# H723ZG_Interface.net
KiCad netlist of a schematic drawn in Altium Designer
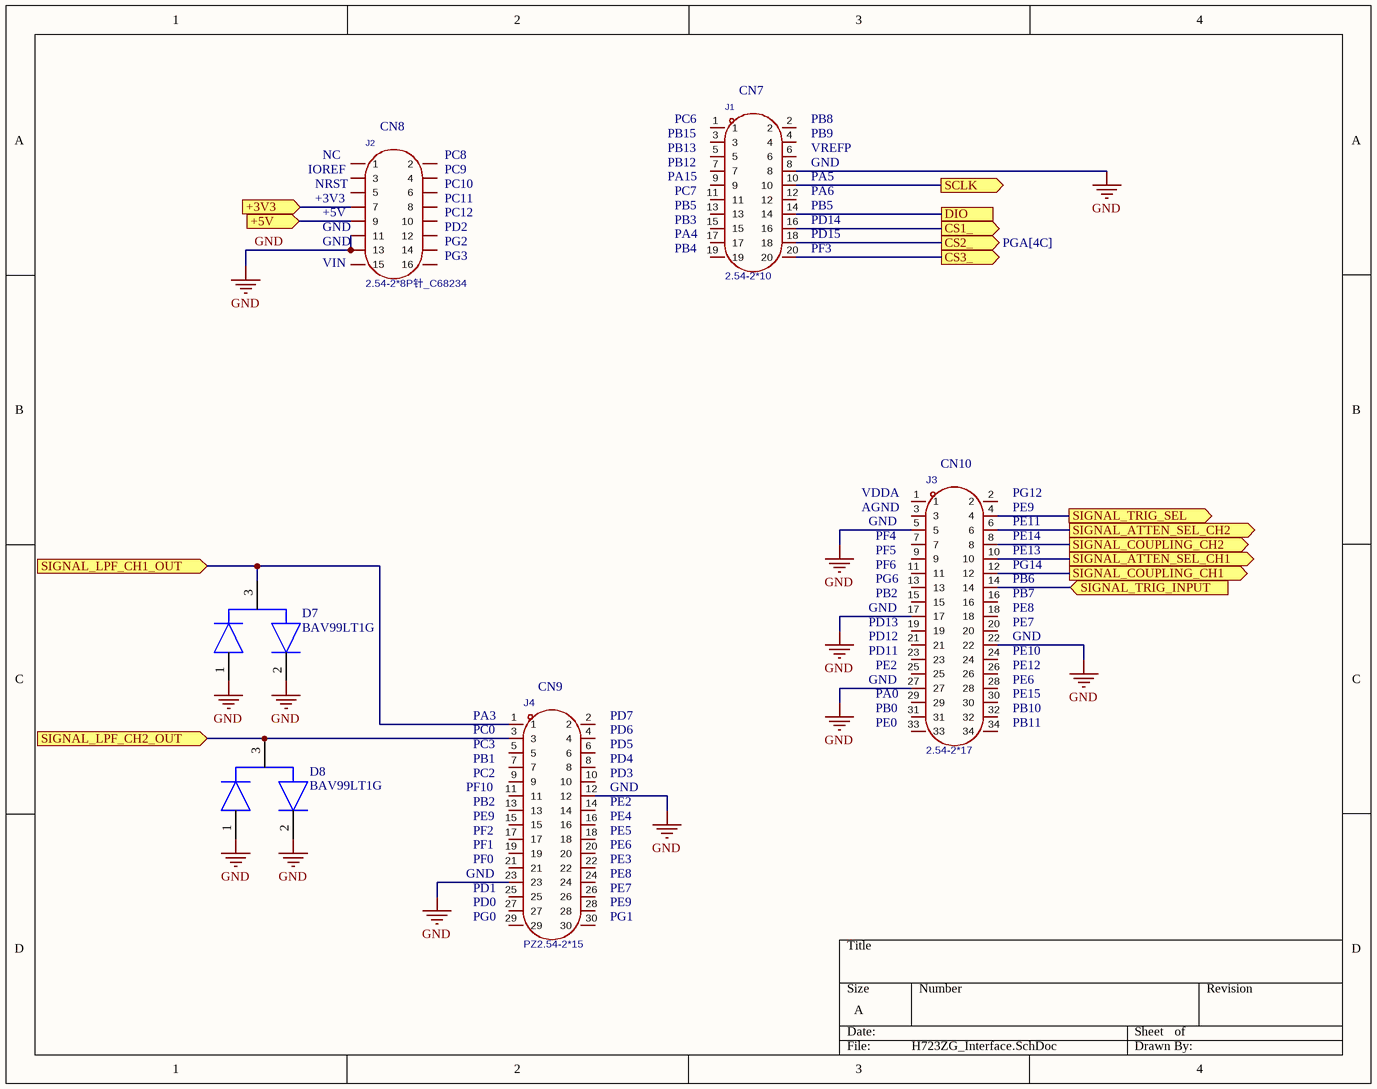
[diagram p0: H723ZG_Interface.SchDoc]

(export (version "E")
  (design (tool "Eeschema 10.0.6"))
  (components
    (comp (ref "D7")
      (value "BAV99LT1G")
      (footprint "FP-318-08-IPC_B")
      (description "DIODE ARRAY 100V 215MA SOT23-3")
      (libsource (lib "Altium Content Vault") (part "7b418a28e9680f52904df7990ac9ce6"))
    )
    (comp (ref "D8")
      (value "BAV99LT1G")
      (footprint "FP-318-08-IPC_B")
      (description "DIODE ARRAY 100V 215MA SOT23-3")
      (libsource (lib "Altium Content Vault") (part "7b418a28e9680f52904df7990ac9ce6"))
    )
    (comp (ref "J1")
      (value "2.54-2*10")
      (footprint "HDR-TH_20P-P2.54-V-M-R2-C10-S2.54")
      (fields (field (name "MANUFACTURER") "ZHOURI(洲日)"))
      (libsource (lib "zhiming xue") (part "2.54-2*10"))
    )
    (comp (ref "J2")
      (value "2.54-2*8P针_C68234")
      (footprint "HDR-TH_16P-P2.54-V-M-R2-C8-S2.54")
      (fields
        (field (name "MANUFACTURER") "BOOMELE(博穆精密)")
        (field (name "MANUFACTURER PART NUMBER") "2.54-2*8P针")
      )
      (libsource (lib "zhiming xue") (part "2.54-2*8P针_C68234"))
    )
    (comp (ref "J3")
      (value "2.54-2*17")
      (footprint "HDR-TH_34P-P2.54-V-M-R2-C17-S2.54-2")
      (description "2.54mm pitch, 2 rows, 2*17, 34 pins total")
      (libsource (lib "zhiming xue") (part "PZ2.54-2*17"))
    )
    (comp (ref "J4")
      (value "PZ2.54-2*15")
      (footprint "HDR-TH_30P-P2.54-V-M-R2-C15-S2.54-2")
      (fields (field (name "MANUFACTURER") "ZHOURI(洲日)"))
      (libsource (lib "zhiming xue") (part "PZ2.54-2*15"))
    )
  )
  (nets
    (net (code "1") (name "/+3V3") (class "Default")
      (node (ref "J2") (pin "7") (pinfunction "7_7") (pintype "passive"))
    )
    (net (code "2") (name "/+5V") (class "Default")
      (node (ref "J2") (pin "9") (pinfunction "9_9") (pintype "passive"))
    )
    (net (code "3") (name "/CS1_") (class "Default")
      (node (ref "J1") (pin "16") (pinfunction "16_16") (pintype "passive"))
    )
    (net (code "4") (name "/CS2_") (class "Default")
      (node (ref "J1") (pin "18") (pinfunction "18_18") (pintype "passive"))
    )
    (net (code "5") (name "/CS3_") (class "Default")
      (node (ref "J1") (pin "20") (pinfunction "20_20") (pintype "passive"))
    )
    (net (code "6") (name "/DIO") (class "Default")
      (node (ref "J1") (pin "14") (pinfunction "14_14") (pintype "passive"))
    )
    (net (code "7") (name "/SCLK") (class "Default")
      (node (ref "J1") (pin "10") (pinfunction "10_10") (pintype "passive"))
    )
    (net (code "8") (name "/SIGNAL_ATTEN_SEL_CH1") (class "Default")
      (node (ref "J3") (pin "10") (pinfunction "10_10") (pintype "passive"))
    )
    (net (code "9") (name "/SIGNAL_ATTEN_SEL_CH2") (class "Default")
      (node (ref "J3") (pin "6") (pinfunction "6_6") (pintype "passive"))
    )
    (net (code "10") (name "/SIGNAL_COUPLING_CH1") (class "Default")
      (node (ref "J3") (pin "12") (pinfunction "12_12") (pintype "passive"))
    )
    (net (code "11") (name "/SIGNAL_COUPLING_CH2") (class "Default")
      (node (ref "J3") (pin "8") (pinfunction "8_8") (pintype "passive"))
    )
    (net (code "12") (name "/SIGNAL_LPF_CH1_OUT") (class "Default")
      (node (ref "D7") (pin "3") (pinfunction "CATHODE/ANODE_3") (pintype "passive"))
      (node (ref "J4") (pin "1") (pinfunction "1_1") (pintype "passive"))
    )
    (net (code "13") (name "/SIGNAL_LPF_CH2_OUT") (class "Default")
      (node (ref "D8") (pin "3") (pinfunction "CATHODE/ANODE_3") (pintype "passive"))
      (node (ref "J4") (pin "3") (pinfunction "3_3") (pintype "passive"))
    )
    (net (code "14") (name "/SIGNAL_TRIG_INPUT") (class "Default")
      (node (ref "J3") (pin "14") (pinfunction "14_14") (pintype "passive"))
    )
    (net (code "15") (name "/SIGNAL_TRIG_SEL") (class "Default")
      (node (ref "J3") (pin "4") (pinfunction "4_4") (pintype "passive"))
    )
    (net (code "16") (name "GND") (class "Default")
      (node (ref "D7") (pin "1") (pinfunction "A_1") (pintype "passive"))
      (node (ref "D7") (pin "2") (pinfunction "C_2") (pintype "passive"))
      (node (ref "D8") (pin "1") (pinfunction "A_1") (pintype "passive"))
      (node (ref "D8") (pin "2") (pinfunction "C_2") (pintype "passive"))
      (node (ref "J1") (pin "8") (pinfunction "8_8") (pintype "passive"))
      (node (ref "J2") (pin "11") (pinfunction "11_11") (pintype "passive"))
      (node (ref "J2") (pin "13") (pinfunction "13_13") (pintype "passive"))
      (node (ref "J3") (pin "17") (pinfunction "17_17") (pintype "passive"))
      (node (ref "J3") (pin "22") (pinfunction "22_22") (pintype "passive"))
      (node (ref "J3") (pin "27") (pinfunction "27_27") (pintype "passive"))
      (node (ref "J3") (pin "5") (pinfunction "5_5") (pintype "passive"))
      (node (ref "J4") (pin "12") (pinfunction "12_12") (pintype "passive"))
      (node (ref "J4") (pin "23") (pinfunction "23_23") (pintype "passive"))
    )
    (net (code "17") (name "unconnected-(J1-Pad1)") (class "Default")
      (node (ref "J1") (pin "1") (pinfunction "1_1") (pintype "passive"))
    )
    (net (code "18") (name "unconnected-(J1-Pad2)") (class "Default")
      (node (ref "J1") (pin "2") (pinfunction "2_2") (pintype "passive"))
    )
    (net (code "19") (name "unconnected-(J1-Pad3)") (class "Default")
      (node (ref "J1") (pin "3") (pinfunction "3_3") (pintype "passive"))
    )
    (net (code "20") (name "unconnected-(J1-Pad4)") (class "Default")
      (node (ref "J1") (pin "4") (pinfunction "4_4") (pintype "passive"))
    )
    (net (code "21") (name "unconnected-(J1-Pad5)") (class "Default")
      (node (ref "J1") (pin "5") (pinfunction "5_5") (pintype "passive"))
    )
    (net (code "22") (name "unconnected-(J1-Pad6)") (class "Default")
      (node (ref "J1") (pin "6") (pinfunction "6_6") (pintype "passive"))
    )
    (net (code "23") (name "unconnected-(J1-Pad7)") (class "Default")
      (node (ref "J1") (pin "7") (pinfunction "7_7") (pintype "passive"))
    )
    (net (code "24") (name "unconnected-(J1-Pad9)") (class "Default")
      (node (ref "J1") (pin "9") (pinfunction "9_9") (pintype "passive"))
    )
    (net (code "25") (name "unconnected-(J1-Pad11)") (class "Default")
      (node (ref "J1") (pin "11") (pinfunction "11_11") (pintype "passive"))
    )
    (net (code "26") (name "unconnected-(J1-Pad12)") (class "Default")
      (node (ref "J1") (pin "12") (pinfunction "12_12") (pintype "passive"))
    )
    (net (code "27") (name "unconnected-(J1-Pad13)") (class "Default")
      (node (ref "J1") (pin "13") (pinfunction "13_13") (pintype "passive"))
    )
    (net (code "28") (name "unconnected-(J1-Pad15)") (class "Default")
      (node (ref "J1") (pin "15") (pinfunction "15_15") (pintype "passive"))
    )
    (net (code "29") (name "unconnected-(J1-Pad17)") (class "Default")
      (node (ref "J1") (pin "17") (pinfunction "17_17") (pintype "passive"))
    )
    (net (code "30") (name "unconnected-(J1-Pad19)") (class "Default")
      (node (ref "J1") (pin "19") (pinfunction "19_19") (pintype "passive"))
    )
    (net (code "31") (name "unconnected-(J2-Pad1)") (class "Default")
      (node (ref "J2") (pin "1") (pinfunction "1_1") (pintype "passive"))
    )
    (net (code "32") (name "unconnected-(J2-Pad2)") (class "Default")
      (node (ref "J2") (pin "2") (pinfunction "2_2") (pintype "passive"))
    )
    (net (code "33") (name "unconnected-(J2-Pad3)") (class "Default")
      (node (ref "J2") (pin "3") (pinfunction "3_3") (pintype "passive"))
    )
    (net (code "34") (name "unconnected-(J2-Pad4)") (class "Default")
      (node (ref "J2") (pin "4") (pinfunction "4_4") (pintype "passive"))
    )
    (net (code "35") (name "unconnected-(J2-Pad5)") (class "Default")
      (node (ref "J2") (pin "5") (pinfunction "5_5") (pintype "passive"))
    )
    (net (code "36") (name "unconnected-(J2-Pad6)") (class "Default")
      (node (ref "J2") (pin "6") (pinfunction "6_6") (pintype "passive"))
    )
    (net (code "37") (name "unconnected-(J2-Pad8)") (class "Default")
      (node (ref "J2") (pin "8") (pinfunction "8_8") (pintype "passive"))
    )
    (net (code "38") (name "unconnected-(J2-Pad10)") (class "Default")
      (node (ref "J2") (pin "10") (pinfunction "10_10") (pintype "passive"))
    )
    (net (code "39") (name "unconnected-(J2-Pad12)") (class "Default")
      (node (ref "J2") (pin "12") (pinfunction "12_12") (pintype "passive"))
    )
    (net (code "40") (name "unconnected-(J2-Pad14)") (class "Default")
      (node (ref "J2") (pin "14") (pinfunction "14_14") (pintype "passive"))
    )
    (net (code "41") (name "unconnected-(J2-Pad15)") (class "Default")
      (node (ref "J2") (pin "15") (pinfunction "15_15") (pintype "passive"))
    )
    (net (code "42") (name "unconnected-(J2-Pad16)") (class "Default")
      (node (ref "J2") (pin "16") (pinfunction "16_16") (pintype "passive"))
    )
    (net (code "43") (name "unconnected-(J3-Pad1)") (class "Default")
      (node (ref "J3") (pin "1") (pinfunction "1_1") (pintype "passive"))
    )
    (net (code "44") (name "unconnected-(J3-Pad2)") (class "Default")
      (node (ref "J3") (pin "2") (pinfunction "2_2") (pintype "passive"))
    )
    (net (code "45") (name "unconnected-(J3-Pad3)") (class "Default")
      (node (ref "J3") (pin "3") (pinfunction "3_3") (pintype "passive"))
    )
    (net (code "46") (name "unconnected-(J3-Pad7)") (class "Default")
      (node (ref "J3") (pin "7") (pinfunction "7_7") (pintype "passive"))
    )
    (net (code "47") (name "unconnected-(J3-Pad9)") (class "Default")
      (node (ref "J3") (pin "9") (pinfunction "9_9") (pintype "passive"))
    )
    (net (code "48") (name "unconnected-(J3-Pad11)") (class "Default")
      (node (ref "J3") (pin "11") (pinfunction "11_11") (pintype "passive"))
    )
    (net (code "49") (name "unconnected-(J3-Pad13)") (class "Default")
      (node (ref "J3") (pin "13") (pinfunction "13_13") (pintype "passive"))
    )
    (net (code "50") (name "unconnected-(J3-Pad15)") (class "Default")
      (node (ref "J3") (pin "15") (pinfunction "15_15") (pintype "passive"))
    )
    (net (code "51") (name "unconnected-(J3-Pad16)") (class "Default")
      (node (ref "J3") (pin "16") (pinfunction "16_16") (pintype "passive"))
    )
    (net (code "52") (name "unconnected-(J3-Pad18)") (class "Default")
      (node (ref "J3") (pin "18") (pinfunction "18_18") (pintype "passive"))
    )
    (net (code "53") (name "unconnected-(J3-Pad19)") (class "Default")
      (node (ref "J3") (pin "19") (pinfunction "19_19") (pintype "passive"))
    )
    (net (code "54") (name "unconnected-(J3-Pad20)") (class "Default")
      (node (ref "J3") (pin "20") (pinfunction "20_20") (pintype "passive"))
    )
    (net (code "55") (name "unconnected-(J3-Pad21)") (class "Default")
      (node (ref "J3") (pin "21") (pinfunction "21_21") (pintype "passive"))
    )
    (net (code "56") (name "unconnected-(J3-Pad23)") (class "Default")
      (node (ref "J3") (pin "23") (pinfunction "23_23") (pintype "passive"))
    )
    (net (code "57") (name "unconnected-(J3-Pad24)") (class "Default")
      (node (ref "J3") (pin "24") (pinfunction "24_24") (pintype "passive"))
    )
    (net (code "58") (name "unconnected-(J3-Pad25)") (class "Default")
      (node (ref "J3") (pin "25") (pinfunction "25_25") (pintype "passive"))
    )
    (net (code "59") (name "unconnected-(J3-Pad26)") (class "Default")
      (node (ref "J3") (pin "26") (pinfunction "26_26") (pintype "passive"))
    )
    (net (code "60") (name "unconnected-(J3-Pad28)") (class "Default")
      (node (ref "J3") (pin "28") (pinfunction "28_28") (pintype "passive"))
    )
    (net (code "61") (name "unconnected-(J3-Pad29)") (class "Default")
      (node (ref "J3") (pin "29") (pinfunction "29_29") (pintype "passive"))
    )
    (net (code "62") (name "unconnected-(J3-Pad30)") (class "Default")
      (node (ref "J3") (pin "30") (pinfunction "30_30") (pintype "passive"))
    )
    (net (code "63") (name "unconnected-(J3-Pad31)") (class "Default")
      (node (ref "J3") (pin "31") (pinfunction "31_31") (pintype "passive"))
    )
    (net (code "64") (name "unconnected-(J3-Pad32)") (class "Default")
      (node (ref "J3") (pin "32") (pinfunction "32_32") (pintype "passive"))
    )
    (net (code "65") (name "unconnected-(J3-Pad33)") (class "Default")
      (node (ref "J3") (pin "33") (pinfunction "33_33") (pintype "passive"))
    )
    (net (code "66") (name "unconnected-(J3-Pad34)") (class "Default")
      (node (ref "J3") (pin "34") (pinfunction "34_34") (pintype "passive"))
    )
    (net (code "67") (name "unconnected-(J4-Pad2)") (class "Default")
      (node (ref "J4") (pin "2") (pinfunction "2_2") (pintype "passive"))
    )
    (net (code "68") (name "unconnected-(J4-Pad4)") (class "Default")
      (node (ref "J4") (pin "4") (pinfunction "4_4") (pintype "passive"))
    )
    (net (code "69") (name "unconnected-(J4-Pad5)") (class "Default")
      (node (ref "J4") (pin "5") (pinfunction "5_5") (pintype "passive"))
    )
    (net (code "70") (name "unconnected-(J4-Pad6)") (class "Default")
      (node (ref "J4") (pin "6") (pinfunction "6_6") (pintype "passive"))
    )
    (net (code "71") (name "unconnected-(J4-Pad7)") (class "Default")
      (node (ref "J4") (pin "7") (pinfunction "7_7") (pintype "passive"))
    )
    (net (code "72") (name "unconnected-(J4-Pad8)") (class "Default")
      (node (ref "J4") (pin "8") (pinfunction "8_8") (pintype "passive"))
    )
    (net (code "73") (name "unconnected-(J4-Pad9)") (class "Default")
      (node (ref "J4") (pin "9") (pinfunction "9_9") (pintype "passive"))
    )
    (net (code "74") (name "unconnected-(J4-Pad10)") (class "Default")
      (node (ref "J4") (pin "10") (pinfunction "10_10") (pintype "passive"))
    )
    (net (code "75") (name "unconnected-(J4-Pad11)") (class "Default")
      (node (ref "J4") (pin "11") (pinfunction "11_11") (pintype "passive"))
    )
    (net (code "76") (name "unconnected-(J4-Pad13)") (class "Default")
      (node (ref "J4") (pin "13") (pinfunction "13_13") (pintype "passive"))
    )
    (net (code "77") (name "unconnected-(J4-Pad14)") (class "Default")
      (node (ref "J4") (pin "14") (pinfunction "14_14") (pintype "passive"))
    )
    (net (code "78") (name "unconnected-(J4-Pad15)") (class "Default")
      (node (ref "J4") (pin "15") (pinfunction "15_15") (pintype "passive"))
    )
    (net (code "79") (name "unconnected-(J4-Pad16)") (class "Default")
      (node (ref "J4") (pin "16") (pinfunction "16_16") (pintype "passive"))
    )
    (net (code "80") (name "unconnected-(J4-Pad17)") (class "Default")
      (node (ref "J4") (pin "17") (pinfunction "17_17") (pintype "passive"))
    )
    (net (code "81") (name "unconnected-(J4-Pad18)") (class "Default")
      (node (ref "J4") (pin "18") (pinfunction "18_18") (pintype "passive"))
    )
    (net (code "82") (name "unconnected-(J4-Pad19)") (class "Default")
      (node (ref "J4") (pin "19") (pinfunction "19_19") (pintype "passive"))
    )
    (net (code "83") (name "unconnected-(J4-Pad20)") (class "Default")
      (node (ref "J4") (pin "20") (pinfunction "20_20") (pintype "passive"))
    )
    (net (code "84") (name "unconnected-(J4-Pad21)") (class "Default")
      (node (ref "J4") (pin "21") (pinfunction "21_21") (pintype "passive"))
    )
    (net (code "85") (name "unconnected-(J4-Pad22)") (class "Default")
      (node (ref "J4") (pin "22") (pinfunction "22_22") (pintype "passive"))
    )
    (net (code "86") (name "unconnected-(J4-Pad24)") (class "Default")
      (node (ref "J4") (pin "24") (pinfunction "24_24") (pintype "passive"))
    )
    (net (code "87") (name "unconnected-(J4-Pad25)") (class "Default")
      (node (ref "J4") (pin "25") (pinfunction "25_25") (pintype "passive"))
    )
    (net (code "88") (name "unconnected-(J4-Pad26)") (class "Default")
      (node (ref "J4") (pin "26") (pinfunction "26_26") (pintype "passive"))
    )
    (net (code "89") (name "unconnected-(J4-Pad27)") (class "Default")
      (node (ref "J4") (pin "27") (pinfunction "27_27") (pintype "passive"))
    )
    (net (code "90") (name "unconnected-(J4-Pad28)") (class "Default")
      (node (ref "J4") (pin "28") (pinfunction "28_28") (pintype "passive"))
    )
    (net (code "91") (name "unconnected-(J4-Pad29)") (class "Default")
      (node (ref "J4") (pin "29") (pinfunction "29_29") (pintype "passive"))
    )
    (net (code "92") (name "unconnected-(J4-Pad30)") (class "Default")
      (node (ref "J4") (pin "30") (pinfunction "30_30") (pintype "passive"))
    )
  )
)
